# SHIELD_TFT.net
KiCad netlist of a schematic drawn in EAGLE
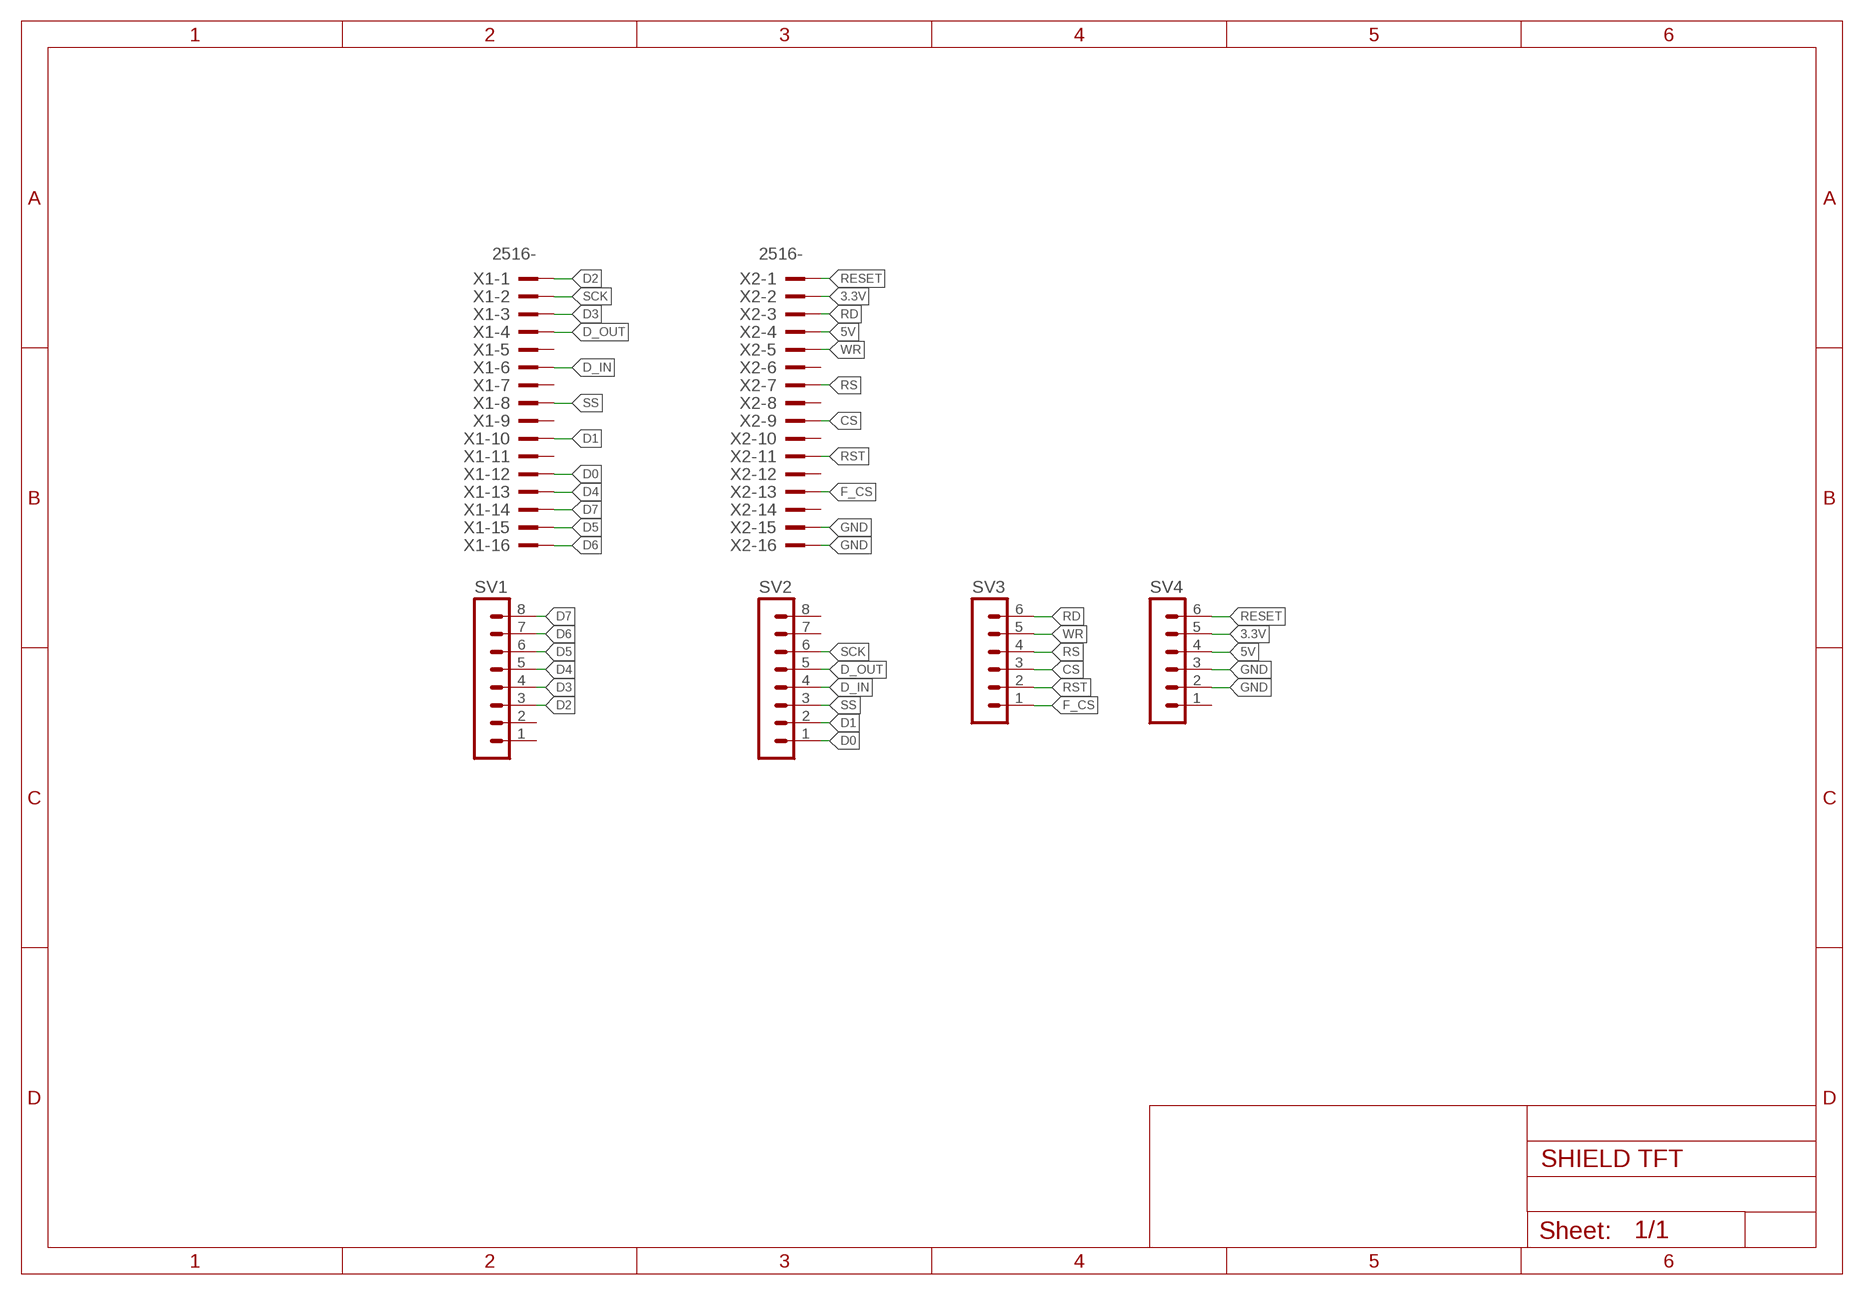
[diagram p0: schematic, sheet 1]

(export (version "E")
  (design (tool "Eeschema 10.0.6"))
  (components
    (comp (ref "SV1")
      (value "MA08-1")
      (footprint "eagle-import:MA08-1")
      (libsource (lib "eagle-import") (part "MA08-1"))
    )
    (comp (ref "SV2")
      (value "MA08-1")
      (footprint "eagle-import:MA08-1")
      (libsource (lib "eagle-import") (part "MA08-1"))
    )
    (comp (ref "SV3")
      (value "MA06-1")
      (footprint "eagle-import:MA06-1")
      (libsource (lib "eagle-import") (part "MA06-1"))
    )
    (comp (ref "SV4")
      (value "MA06-1")
      (footprint "eagle-import:MA06-1")
      (libsource (lib "eagle-import") (part "MA06-1"))
    )
    (comp (ref "X1")
      (value "2516-")
      (footprint "eagle-import:PAK100_2500-16")
      (libsource (lib "eagle-import") (part "2516-"))
    )
    (comp (ref "X2")
      (value "2516-")
      (footprint "eagle-import:PAK100_2500-16")
      (libsource (lib "eagle-import") (part "2516-"))
    )
  )
  (nets
    (net (code "1") (name "3.3V") (class "Default")
      (node (ref "SV4") (pin "5") (pinfunction "5_5") (pintype "passive"))
      (node (ref "X2") (pin "2") (pinfunction "KL_2") (pintype "passive"))
    )
    (net (code "2") (name "5V") (class "Default")
      (node (ref "SV4") (pin "4") (pinfunction "4_4") (pintype "passive"))
      (node (ref "X2") (pin "4") (pinfunction "KL_4") (pintype "passive"))
    )
    (net (code "3") (name "CS") (class "Default")
      (node (ref "SV3") (pin "3") (pinfunction "3_3") (pintype "passive"))
      (node (ref "X2") (pin "9") (pinfunction "KL_9") (pintype "passive"))
    )
    (net (code "4") (name "D0") (class "Default")
      (node (ref "SV2") (pin "1") (pinfunction "1_1") (pintype "passive"))
      (node (ref "X1") (pin "12") (pinfunction "KL_12") (pintype "passive"))
    )
    (net (code "5") (name "D1") (class "Default")
      (node (ref "SV2") (pin "2") (pinfunction "2_2") (pintype "passive"))
      (node (ref "X1") (pin "10") (pinfunction "KL_10") (pintype "passive"))
    )
    (net (code "6") (name "D2") (class "Default")
      (node (ref "SV1") (pin "3") (pinfunction "3_3") (pintype "passive"))
      (node (ref "X1") (pin "1") (pinfunction "KL_1") (pintype "passive"))
    )
    (net (code "7") (name "D3") (class "Default")
      (node (ref "SV1") (pin "4") (pinfunction "4_4") (pintype "passive"))
      (node (ref "X1") (pin "3") (pinfunction "KL_3") (pintype "passive"))
    )
    (net (code "8") (name "D4") (class "Default")
      (node (ref "SV1") (pin "5") (pinfunction "5_5") (pintype "passive"))
      (node (ref "X1") (pin "13") (pinfunction "KL_13") (pintype "passive"))
    )
    (net (code "9") (name "D5") (class "Default")
      (node (ref "SV1") (pin "6") (pinfunction "6_6") (pintype "passive"))
      (node (ref "X1") (pin "15") (pinfunction "KL_15") (pintype "passive"))
    )
    (net (code "10") (name "D6") (class "Default")
      (node (ref "SV1") (pin "7") (pinfunction "7_7") (pintype "passive"))
      (node (ref "X1") (pin "16") (pinfunction "KL_16") (pintype "passive"))
    )
    (net (code "11") (name "D7") (class "Default")
      (node (ref "SV1") (pin "8") (pinfunction "8_8") (pintype "passive"))
      (node (ref "X1") (pin "14") (pinfunction "KL_14") (pintype "passive"))
    )
    (net (code "12") (name "D_IN") (class "Default")
      (node (ref "SV2") (pin "4") (pinfunction "4_4") (pintype "passive"))
      (node (ref "X1") (pin "6") (pinfunction "KL_6") (pintype "passive"))
    )
    (net (code "13") (name "D_OUT") (class "Default")
      (node (ref "SV2") (pin "5") (pinfunction "5_5") (pintype "passive"))
      (node (ref "X1") (pin "4") (pinfunction "KL_4") (pintype "passive"))
    )
    (net (code "14") (name "F_CS") (class "Default")
      (node (ref "SV3") (pin "1") (pinfunction "1_1") (pintype "passive"))
      (node (ref "X2") (pin "13") (pinfunction "KL_13") (pintype "passive"))
    )
    (net (code "15") (name "GND") (class "Default")
      (node (ref "SV4") (pin "2") (pinfunction "2_2") (pintype "passive"))
      (node (ref "SV4") (pin "3") (pinfunction "3_3") (pintype "passive"))
      (node (ref "X2") (pin "15") (pinfunction "KL_15") (pintype "passive"))
      (node (ref "X2") (pin "16") (pinfunction "KL_16") (pintype "passive"))
    )
    (net (code "16") (name "RD") (class "Default")
      (node (ref "SV3") (pin "6") (pinfunction "6_6") (pintype "passive"))
      (node (ref "X2") (pin "3") (pinfunction "KL_3") (pintype "passive"))
    )
    (net (code "17") (name "RESET") (class "Default")
      (node (ref "SV4") (pin "6") (pinfunction "6_6") (pintype "passive"))
      (node (ref "X2") (pin "1") (pinfunction "KL_1") (pintype "passive"))
    )
    (net (code "18") (name "RS") (class "Default")
      (node (ref "SV3") (pin "4") (pinfunction "4_4") (pintype "passive"))
      (node (ref "X2") (pin "7") (pinfunction "KL_7") (pintype "passive"))
    )
    (net (code "19") (name "RST") (class "Default")
      (node (ref "SV3") (pin "2") (pinfunction "2_2") (pintype "passive"))
      (node (ref "X2") (pin "11") (pinfunction "KL_11") (pintype "passive"))
    )
    (net (code "20") (name "SCK") (class "Default")
      (node (ref "SV2") (pin "6") (pinfunction "6_6") (pintype "passive"))
      (node (ref "X1") (pin "2") (pinfunction "KL_2") (pintype "passive"))
    )
    (net (code "21") (name "SS") (class "Default")
      (node (ref "SV2") (pin "3") (pinfunction "3_3") (pintype "passive"))
      (node (ref "X1") (pin "8") (pinfunction "KL_8") (pintype "passive"))
    )
    (net (code "22") (name "WR") (class "Default")
      (node (ref "SV3") (pin "5") (pinfunction "5_5") (pintype "passive"))
      (node (ref "X2") (pin "5") (pinfunction "KL_5") (pintype "passive"))
    )
    (net (code "23") (name "unconnected-(SV1-Pad1)") (class "Default")
      (node (ref "SV1") (pin "1") (pinfunction "1_1") (pintype "passive"))
    )
    (net (code "24") (name "unconnected-(SV1-Pad2)") (class "Default")
      (node (ref "SV1") (pin "2") (pinfunction "2_2") (pintype "passive"))
    )
    (net (code "25") (name "unconnected-(SV2-Pad7)") (class "Default")
      (node (ref "SV2") (pin "7") (pinfunction "7_7") (pintype "passive"))
    )
    (net (code "26") (name "unconnected-(SV2-Pad8)") (class "Default")
      (node (ref "SV2") (pin "8") (pinfunction "8_8") (pintype "passive"))
    )
    (net (code "27") (name "unconnected-(SV4-Pad1)") (class "Default")
      (node (ref "SV4") (pin "1") (pinfunction "1_1") (pintype "passive"))
    )
    (net (code "28") (name "unconnected-(X1C-KL-Pad11)") (class "Default")
      (node (ref "X1") (pin "11") (pinfunction "KL_11") (pintype "passive"))
    )
    (net (code "29") (name "unconnected-(X1L-KL-Pad5)") (class "Default")
      (node (ref "X1") (pin "5") (pinfunction "KL_5") (pintype "passive"))
    )
    (net (code "30") (name "unconnected-(X1N-KL-Pad7)") (class "Default")
      (node (ref "X1") (pin "7") (pinfunction "KL_7") (pintype "passive"))
    )
    (net (code "31") (name "unconnected-(X1P-KL-Pad9)") (class "Default")
      (node (ref "X1") (pin "9") (pinfunction "KL_9") (pintype "passive"))
    )
    (net (code "32") (name "unconnected-(X2B-KL-Pad10)") (class "Default")
      (node (ref "X2") (pin "10") (pinfunction "KL_10") (pintype "passive"))
    )
    (net (code "33") (name "unconnected-(X2D-KL-Pad12)") (class "Default")
      (node (ref "X2") (pin "12") (pinfunction "KL_12") (pintype "passive"))
    )
    (net (code "34") (name "unconnected-(X2F-KL-Pad14)") (class "Default")
      (node (ref "X2") (pin "14") (pinfunction "KL_14") (pintype "passive"))
    )
    (net (code "35") (name "unconnected-(X2M-KL-Pad6)") (class "Default")
      (node (ref "X2") (pin "6") (pinfunction "KL_6") (pintype "passive"))
    )
    (net (code "36") (name "unconnected-(X2O-KL-Pad8)") (class "Default")
      (node (ref "X2") (pin "8") (pinfunction "KL_8") (pintype "passive"))
    )
  )
)
